# BGA-4_Breakout.net
KiCad netlist of a schematic drawn in EAGLE
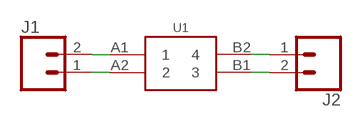
[diagram p0: schematic, sheet 1]

(export (version "E")
  (design (tool "Eeschema 10.0.6"))
  (components
    (comp (ref "J1")
      (value "CONN_02")
      (footprint "eagle-import:1X02")
      (libsource (lib "eagle-import") (part "CONN_02"))
    )
    (comp (ref "J2")
      (value "CONN_02")
      (footprint "eagle-import:1X02")
      (libsource (lib "eagle-import") (part "CONN_02"))
    )
    (comp (ref "U1")
      (value "GEN_4BGA")
      (footprint "eagle-import:YFP0004")
      (libsource (lib "eagle-import") (part "GEN_4BGA"))
    )
  )
  (nets
    (net (code "1") (name "Net-(U1-1)") (class "Default")
      (node (ref "J1") (pin "2") (pinfunction "2_2") (pintype "passive"))
      (node (ref "U1") (pin "A1") (pinfunction "1_A1") (pintype "bidirectional"))
    )
    (net (code "2") (name "Net-(U1-2)") (class "Default")
      (node (ref "J1") (pin "1") (pinfunction "1_1") (pintype "passive"))
      (node (ref "U1") (pin "A2") (pinfunction "2_A2") (pintype "bidirectional"))
    )
    (net (code "3") (name "Net-(U1-3)") (class "Default")
      (node (ref "J2") (pin "2") (pinfunction "2_2") (pintype "passive"))
      (node (ref "U1") (pin "B1") (pinfunction "3_B1") (pintype "bidirectional"))
    )
    (net (code "4") (name "Net-(U1-4)") (class "Default")
      (node (ref "J2") (pin "1") (pinfunction "1_1") (pintype "passive"))
      (node (ref "U1") (pin "B2") (pinfunction "4_B2") (pintype "bidirectional"))
    )
  )
)
